# ADF4351_PLL.net
KiCad netlist of a schematic drawn in Altium Designer
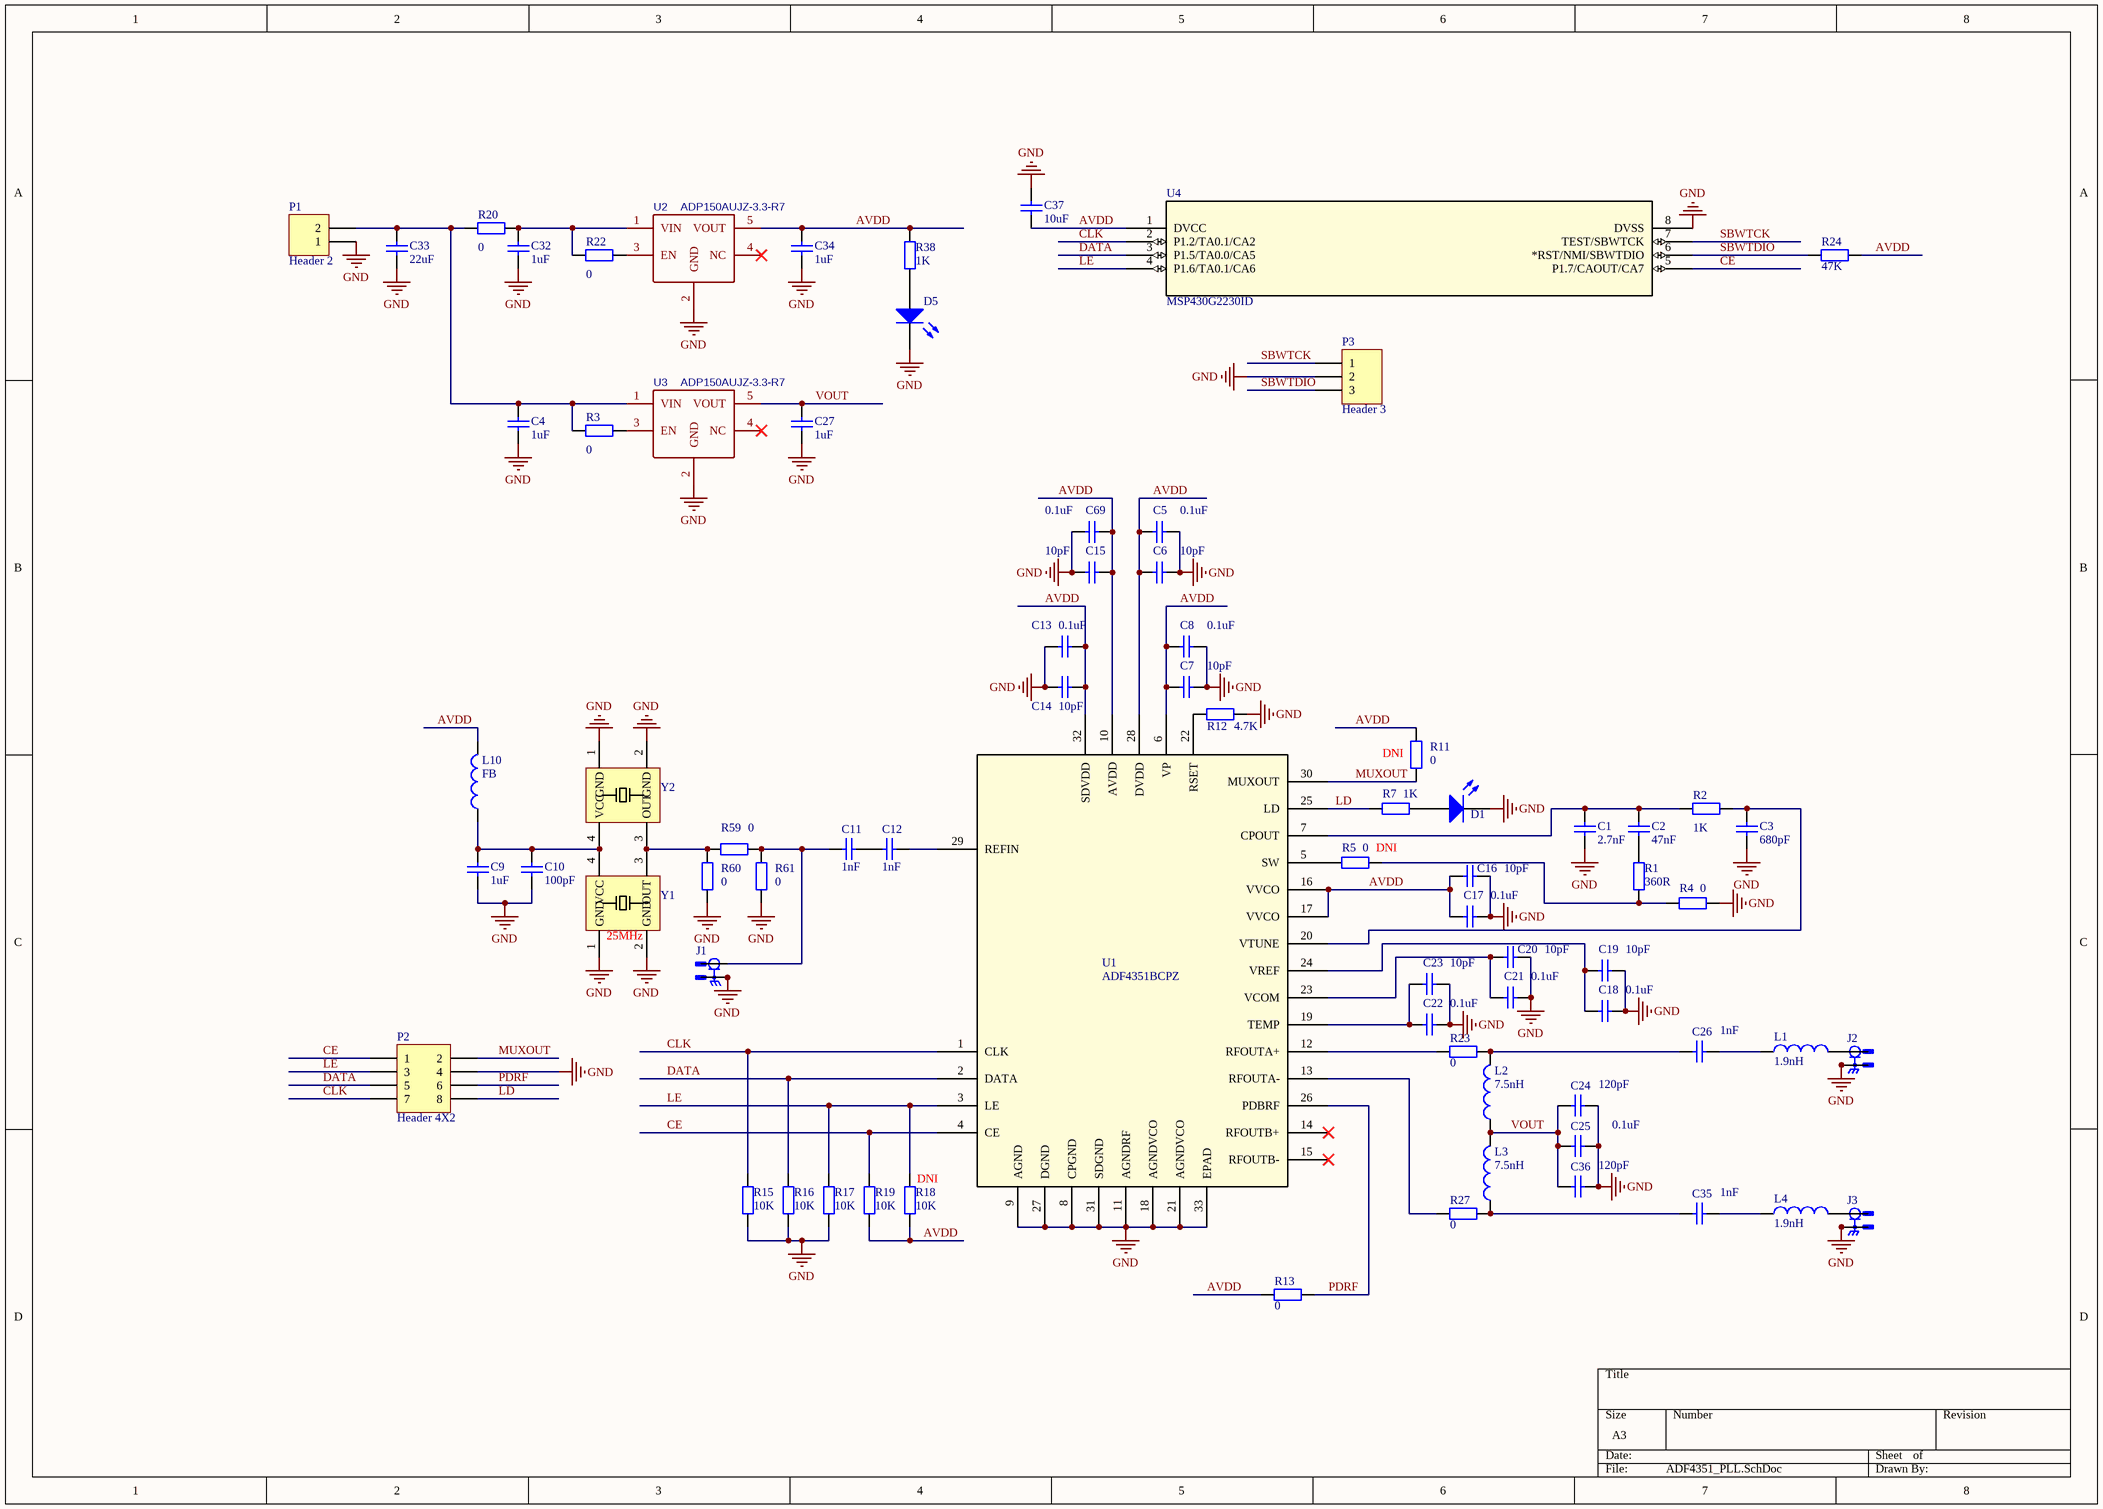
[diagram p0: ADF4351_PLL.SchDoc]

(export (version "E")
  (design (tool "Eeschema 10.0.6"))
  (components
    (comp (ref "C1")
      (value "2.7nF")
      (footprint "0603E")
      (description "Capacitor")
      (fields (field (name "Comment") "Cap") (field (name "PUBLISHER") "Altium Limited"))
      (libsource (lib "Miscellaneous Devices") (part "Cap"))
    )
    (comp (ref "C2")
      (value "47nF")
      (footprint "0603E")
      (description "Capacitor")
      (fields (field (name "Comment") "Cap") (field (name "PUBLISHER") "Altium Limited"))
      (libsource (lib "Miscellaneous Devices") (part "Cap"))
    )
    (comp (ref "C3")
      (value "680pF")
      (footprint "0603E")
      (description "Capacitor")
      (fields (field (name "Comment") "Cap") (field (name "PUBLISHER") "Altium Limited"))
      (libsource (lib "Miscellaneous Devices") (part "Cap"))
    )
    (comp (ref "C4")
      (value "1uF")
      (footprint "0603E")
      (description "Capacitor")
      (fields (field (name "Comment") "Cap") (field (name "PUBLISHER") "Altium Limited"))
      (libsource (lib "Miscellaneous Devices") (part "Cap"))
    )
    (comp (ref "C5")
      (value "0.1uF")
      (footprint "0603E")
      (description "Capacitor")
      (fields (field (name "Comment") "Cap") (field (name "PUBLISHER") "Altium Limited"))
      (libsource (lib "Miscellaneous Devices") (part "Cap"))
    )
    (comp (ref "C6")
      (value "10pF")
      (footprint "0603E")
      (description "Capacitor")
      (fields (field (name "Comment") "Cap") (field (name "PUBLISHER") "Altium Limited"))
      (libsource (lib "Miscellaneous Devices") (part "Cap"))
    )
    (comp (ref "C7")
      (value "10pF")
      (footprint "0603E")
      (description "Capacitor")
      (fields (field (name "Comment") "Cap") (field (name "PUBLISHER") "Altium Limited"))
      (libsource (lib "Miscellaneous Devices") (part "Cap"))
    )
    (comp (ref "C8")
      (value "0.1uF")
      (footprint "0603E")
      (description "Capacitor")
      (fields (field (name "Comment") "Cap") (field (name "PUBLISHER") "Altium Limited"))
      (libsource (lib "Miscellaneous Devices") (part "Cap"))
    )
    (comp (ref "C9")
      (value "1uF")
      (footprint "0603E")
      (description "Capacitor")
      (fields (field (name "Comment") "Cap") (field (name "PUBLISHER") "Altium Limited"))
      (libsource (lib "Miscellaneous Devices") (part "Cap"))
    )
    (comp (ref "C10")
      (value "100pF")
      (footprint "0603E")
      (description "Capacitor")
      (fields (field (name "Comment") "Cap") (field (name "PUBLISHER") "Altium Limited"))
      (libsource (lib "Miscellaneous Devices") (part "Cap"))
    )
    (comp (ref "C11")
      (value "1nF")
      (footprint "0603E")
      (description "Capacitor")
      (fields (field (name "Comment") "Cap") (field (name "PUBLISHER") "Altium Limited"))
      (libsource (lib "Miscellaneous Devices") (part "Cap"))
    )
    (comp (ref "C12")
      (value "1nF")
      (footprint "0603E")
      (description "Capacitor")
      (fields (field (name "Comment") "Cap") (field (name "PUBLISHER") "Altium Limited"))
      (libsource (lib "Miscellaneous Devices") (part "Cap"))
    )
    (comp (ref "C13")
      (value "0.1uF")
      (footprint "0603E")
      (description "Capacitor")
      (fields (field (name "Comment") "Cap") (field (name "PUBLISHER") "Altium Limited"))
      (libsource (lib "Miscellaneous Devices") (part "Cap"))
    )
    (comp (ref "C14")
      (value "10pF")
      (footprint "0603E")
      (description "Capacitor")
      (fields (field (name "Comment") "Cap") (field (name "PUBLISHER") "Altium Limited"))
      (libsource (lib "Miscellaneous Devices") (part "Cap"))
    )
    (comp (ref "C15")
      (value "10pF")
      (footprint "0603E")
      (description "Capacitor")
      (fields (field (name "Comment") "Cap") (field (name "PUBLISHER") "Altium Limited"))
      (libsource (lib "Miscellaneous Devices") (part "Cap"))
    )
    (comp (ref "C16")
      (value "10pF")
      (footprint "0603E")
      (description "Capacitor")
      (fields (field (name "Comment") "Cap") (field (name "PUBLISHER") "Altium Limited"))
      (libsource (lib "Miscellaneous Devices") (part "Cap"))
    )
    (comp (ref "C17")
      (value "0.1uF")
      (footprint "0603E")
      (description "Capacitor")
      (fields (field (name "Comment") "Cap") (field (name "PUBLISHER") "Altium Limited"))
      (libsource (lib "Miscellaneous Devices") (part "Cap"))
    )
    (comp (ref "C18")
      (value "0.1uF")
      (footprint "0603E")
      (description "Capacitor")
      (fields (field (name "Comment") "Cap") (field (name "PUBLISHER") "Altium Limited"))
      (libsource (lib "Miscellaneous Devices") (part "Cap"))
    )
    (comp (ref "C19")
      (value "10pF")
      (footprint "0603E")
      (description "Capacitor")
      (fields (field (name "Comment") "Cap") (field (name "PUBLISHER") "Altium Limited"))
      (libsource (lib "Miscellaneous Devices") (part "Cap"))
    )
    (comp (ref "C20")
      (value "10pF")
      (footprint "0603E")
      (description "Capacitor")
      (fields (field (name "Comment") "Cap") (field (name "PUBLISHER") "Altium Limited"))
      (libsource (lib "Miscellaneous Devices") (part "Cap"))
    )
    (comp (ref "C21")
      (value "0.1uF")
      (footprint "0603E")
      (description "Capacitor")
      (fields (field (name "Comment") "Cap") (field (name "PUBLISHER") "Altium Limited"))
      (libsource (lib "Miscellaneous Devices") (part "Cap"))
    )
    (comp (ref "C22")
      (value "0.1uF")
      (footprint "0603E")
      (description "Capacitor")
      (fields (field (name "Comment") "Cap") (field (name "PUBLISHER") "Altium Limited"))
      (libsource (lib "Miscellaneous Devices") (part "Cap"))
    )
    (comp (ref "C23")
      (value "10pF")
      (footprint "0603E")
      (description "Capacitor")
      (fields (field (name "Comment") "Cap") (field (name "PUBLISHER") "Altium Limited"))
      (libsource (lib "Miscellaneous Devices") (part "Cap"))
    )
    (comp (ref "C24")
      (value "120pF")
      (footprint "0603E")
      (description "Capacitor")
      (fields (field (name "Comment") "Cap") (field (name "PUBLISHER") "Altium Limited"))
      (libsource (lib "Miscellaneous Devices") (part "Cap"))
    )
    (comp (ref "C25")
      (value "0.1uF")
      (footprint "0603E")
      (description "Capacitor")
      (fields (field (name "Comment") "Cap") (field (name "PUBLISHER") "Altium Limited"))
      (libsource (lib "Miscellaneous Devices") (part "Cap"))
    )
    (comp (ref "C26")
      (value "1nF")
      (footprint "0603E")
      (description "Capacitor")
      (fields (field (name "Comment") "Cap") (field (name "PUBLISHER") "Altium Limited"))
      (libsource (lib "Miscellaneous Devices") (part "Cap"))
    )
    (comp (ref "C27")
      (value "1uF")
      (footprint "0603E")
      (description "Capacitor")
      (fields (field (name "Comment") "Cap") (field (name "PUBLISHER") "Altium Limited"))
      (libsource (lib "Miscellaneous Devices") (part "Cap"))
    )
    (comp (ref "C32")
      (value "1uF")
      (footprint "0603E")
      (description "Capacitor")
      (fields (field (name "Comment") "Cap") (field (name "PUBLISHER") "Altium Limited"))
      (libsource (lib "Miscellaneous Devices") (part "Cap"))
    )
    (comp (ref "C33")
      (value "22uF")
      (footprint "R1206")
      (description "Capacitor")
      (fields (field (name "Comment") "Cap") (field (name "PUBLISHER") "Altium Limited"))
      (libsource (lib "Miscellaneous Devices") (part "Cap"))
    )
    (comp (ref "C34")
      (value "1uF")
      (footprint "0603E")
      (description "Capacitor")
      (fields (field (name "Comment") "Cap") (field (name "PUBLISHER") "Altium Limited"))
      (libsource (lib "Miscellaneous Devices") (part "Cap"))
    )
    (comp (ref "C35")
      (value "1nF")
      (footprint "0603E")
      (description "Capacitor")
      (fields (field (name "Comment") "Cap") (field (name "PUBLISHER") "Altium Limited"))
      (libsource (lib "Miscellaneous Devices") (part "Cap"))
    )
    (comp (ref "C36")
      (value "120pF")
      (footprint "0603E")
      (description "Capacitor")
      (fields (field (name "Comment") "Cap") (field (name "PUBLISHER") "Altium Limited"))
      (libsource (lib "Miscellaneous Devices") (part "Cap"))
    )
    (comp (ref "C37")
      (value "10uF")
      (footprint "0603E")
      (description "Capacitor")
      (fields (field (name "Comment") "Cap") (field (name "PUBLISHER") "Altium Limited"))
      (libsource (lib "Miscellaneous Devices") (part "Cap"))
    )
    (comp (ref "C69")
      (value "0.1uF")
      (footprint "0603E")
      (description "Capacitor")
      (fields (field (name "Comment") "Cap") (field (name "PUBLISHER") "Altium Limited"))
      (libsource (lib "Miscellaneous Devices") (part "Cap"))
    )
    (comp (ref "D1")
      (value "LED0")
      (footprint "0603E")
      (description "Typical INFRARED GaAs LED")
      (fields (field (name "PUBLISHER") "Altium Limited"))
      (libsource (lib "Miscellaneous Devices") (part "LED0"))
    )
    (comp (ref "D5")
      (value "LED0")
      (footprint "0603E")
      (description "Typical INFRARED GaAs LED")
      (fields (field (name "PUBLISHER") "Altium Limited"))
      (libsource (lib "Miscellaneous Devices") (part "LED0"))
    )
    (comp (ref "J1")
      (value "~")
      (footprint "SMA")
      (description "SMA Connector Plug, Male Pin 50Ohm Board Edge, End Launch; Panel Mount Solder")
      (fields (field (name "MF") "Linx") (field (name "MP") "CONSMA013.031"))
      (libsource (lib "") (part "CONSMA013.031_1"))
    )
    (comp (ref "J2")
      (value "~")
      (footprint "SMA")
      (description "SMA Connector Plug, Male Pin 50Ohm Board Edge, End Launch; Panel Mount Solder")
      (fields (field (name "MF") "Linx") (field (name "MP") "CONSMA013.031"))
      (libsource (lib "SMA") (part "CONSMA013.031"))
    )
    (comp (ref "J3")
      (value "~")
      (footprint "SMA")
      (description "SMA Connector Plug, Male Pin 50Ohm Board Edge, End Launch; Panel Mount Solder")
      (fields (field (name "MF") "Linx") (field (name "MP") "CONSMA013.031"))
      (libsource (lib "SMA") (part "CONSMA013.031"))
    )
    (comp (ref "L1")
      (value "1.9nH")
      (footprint "0603E")
      (description "Inductor")
      (fields (field (name "PUBLISHER") "Altium Limited"))
      (libsource (lib "Miscellaneous Devices") (part "Inductor"))
    )
    (comp (ref "L2")
      (value "7.5nH")
      (footprint "0603E")
      (description "Inductor")
      (fields (field (name "PUBLISHER") "Altium Limited"))
      (libsource (lib "Miscellaneous Devices") (part "Inductor"))
    )
    (comp (ref "L3")
      (value "7.5nH")
      (footprint "0603E")
      (description "Inductor")
      (fields (field (name "PUBLISHER") "Altium Limited"))
      (libsource (lib "Miscellaneous Devices") (part "Inductor"))
    )
    (comp (ref "L4")
      (value "1.9nH")
      (footprint "0603E")
      (description "Inductor")
      (fields (field (name "PUBLISHER") "Altium Limited"))
      (libsource (lib "Miscellaneous Devices") (part "Inductor"))
    )
    (comp (ref "L10")
      (value "FB")
      (footprint "0603E")
      (description "Inductor")
      (fields (field (name "PUBLISHER") "Altium Limited"))
      (libsource (lib "Miscellaneous Devices") (part "Inductor"))
    )
    (comp (ref "P1")
      (value "Header 2")
      (footprint "HDR1X2")
      (description "Header, 2-Pin")
      (fields (field (name "PUBLISHER") "Altium Limited"))
      (libsource (lib "Miscellaneous Connectors") (part "Header 2"))
    )
    (comp (ref "P2")
      (value "Header 4X2")
      (footprint "HDR2X4")
      (description "Header, 4-Pin, Dual row")
      (fields (field (name "PUBLISHER") "Altium Limited"))
      (libsource (lib "Miscellaneous Connectors") (part "Header 4X2"))
    )
    (comp (ref "P3")
      (value "Header 3")
      (footprint "HDR1X3")
      (description "Header, 3-Pin")
      (fields (field (name "PUBLISHER") "Altium Limited"))
      (libsource (lib "Miscellaneous Connectors") (part "Header 3"))
    )
    (comp (ref "R1")
      (value "360R")
      (footprint "0603E")
      (description "Resistor")
      (fields (field (name "Comment") "Res2") (field (name "PUBLISHER") "Altium Limited"))
      (libsource (lib "Miscellaneous Devices") (part "Res2"))
    )
    (comp (ref "R2")
      (value "1K")
      (footprint "0603E")
      (description "Resistor")
      (fields (field (name "Comment") "Res2") (field (name "PUBLISHER") "Altium Limited"))
      (libsource (lib "") (part "Res2_2"))
    )
    (comp (ref "R3")
      (value "0")
      (footprint "0603E")
      (description "Resistor")
      (fields (field (name "Comment") "Res2") (field (name "PUBLISHER") "Altium Limited"))
      (libsource (lib "") (part "Res2_2"))
    )
    (comp (ref "R4")
      (value "0")
      (footprint "0603E")
      (description "Resistor")
      (fields (field (name "Comment") "Res2") (field (name "PUBLISHER") "Altium Limited"))
      (libsource (lib "") (part "Res2_2"))
    )
    (comp (ref "R5")
      (value "0")
      (footprint "0603E")
      (description "Resistor")
      (fields (field (name "Comment") "Res2") (field (name "PUBLISHER") "Altium Limited"))
      (libsource (lib "") (part "Res2_2"))
    )
    (comp (ref "R7")
      (value "1K")
      (footprint "0603E")
      (description "Resistor")
      (fields (field (name "Comment") "Res2") (field (name "PUBLISHER") "Altium Limited"))
      (libsource (lib "") (part "Res2_2"))
    )
    (comp (ref "R11")
      (value "0")
      (footprint "0603E")
      (description "Resistor")
      (fields (field (name "Comment") "Res2") (field (name "PUBLISHER") "Altium Limited"))
      (libsource (lib "Miscellaneous Devices") (part "Res2"))
    )
    (comp (ref "R12")
      (value "4.7K")
      (footprint "0603E")
      (description "Resistor")
      (fields (field (name "Comment") "Res2") (field (name "PUBLISHER") "Altium Limited"))
      (libsource (lib "") (part "Res2_1"))
    )
    (comp (ref "R13")
      (value "0")
      (footprint "0603E")
      (description "Resistor")
      (fields (field (name "Comment") "Res2") (field (name "PUBLISHER") "Altium Limited"))
      (libsource (lib "") (part "Res2_1"))
    )
    (comp (ref "R15")
      (value "10K")
      (footprint "0603E")
      (description "Resistor")
      (fields (field (name "Comment") "Res2") (field (name "PUBLISHER") "Altium Limited"))
      (libsource (lib "Miscellaneous Devices") (part "Res2"))
    )
    (comp (ref "R16")
      (value "10K")
      (footprint "0603E")
      (description "Resistor")
      (fields (field (name "Comment") "Res2") (field (name "PUBLISHER") "Altium Limited"))
      (libsource (lib "Miscellaneous Devices") (part "Res2"))
    )
    (comp (ref "R17")
      (value "10K")
      (footprint "0603E")
      (description "Resistor")
      (fields (field (name "Comment") "Res2") (field (name "PUBLISHER") "Altium Limited"))
      (libsource (lib "Miscellaneous Devices") (part "Res2"))
    )
    (comp (ref "R18")
      (value "10K")
      (footprint "0603E")
      (description "Resistor")
      (fields (field (name "Comment") "Res2") (field (name "PUBLISHER") "Altium Limited"))
      (libsource (lib "Miscellaneous Devices") (part "Res2"))
    )
    (comp (ref "R19")
      (value "10K")
      (footprint "0603E")
      (description "Resistor")
      (fields (field (name "Comment") "Res2") (field (name "PUBLISHER") "Altium Limited"))
      (libsource (lib "Miscellaneous Devices") (part "Res2"))
    )
    (comp (ref "R20")
      (value "0")
      (footprint "0603E")
      (description "Resistor")
      (fields (field (name "Comment") "Res2") (field (name "PUBLISHER") "Altium Limited"))
      (libsource (lib "") (part "Res2_2"))
    )
    (comp (ref "R22")
      (value "0")
      (footprint "0603E")
      (description "Resistor")
      (fields (field (name "Comment") "Res2") (field (name "PUBLISHER") "Altium Limited"))
      (libsource (lib "") (part "Res2_2"))
    )
    (comp (ref "R23")
      (value "0")
      (footprint "0603E")
      (description "Resistor")
      (fields (field (name "Comment") "Res2") (field (name "PUBLISHER") "Altium Limited"))
      (libsource (lib "") (part "Res2_1"))
    )
    (comp (ref "R24")
      (value "47K")
      (footprint "0603E")
      (description "Resistor")
      (fields (field (name "Comment") "Res2") (field (name "PUBLISHER") "Altium Limited"))
      (libsource (lib "") (part "Res2_2"))
    )
    (comp (ref "R27")
      (value "0")
      (footprint "0603E")
      (description "Resistor")
      (fields (field (name "Comment") "Res2") (field (name "PUBLISHER") "Altium Limited"))
      (libsource (lib "") (part "Res2_1"))
    )
    (comp (ref "R38")
      (value "1K")
      (footprint "0603E")
      (description "Resistor")
      (fields (field (name "Comment") "Res2") (field (name "PUBLISHER") "Altium Limited"))
      (libsource (lib "Miscellaneous Devices") (part "Res2"))
    )
    (comp (ref "R59")
      (value "0")
      (footprint "0603E")
      (description "Resistor")
      (fields (field (name "Comment") "Res2") (field (name "PUBLISHER") "Altium Limited"))
      (libsource (lib "") (part "Res2_2"))
    )
    (comp (ref "R60")
      (value "0")
      (footprint "0603E")
      (description "Resistor")
      (fields (field (name "Comment") "Res2") (field (name "PUBLISHER") "Altium Limited"))
      (libsource (lib "Miscellaneous Devices") (part "Res2"))
    )
    (comp (ref "R61")
      (value "0")
      (footprint "0603E")
      (description "Resistor")
      (fields (field (name "Comment") "Res2") (field (name "PUBLISHER") "Altium Limited"))
      (libsource (lib "Miscellaneous Devices") (part "Res2"))
    )
    (comp (ref "U1")
      (value "ADF4351BCPZ")
      (footprint "CP-32-7_ADI")
      (description "No Description Available")
      (fields (field (name "COPYRIGHT") "Copyright (C) 2021 Accelerated Designs. All rights reserved"))
      (libsource (lib "ADF4351BCPZ") (part "ADF4351BCPZ"))
    )
    (comp (ref "U2")
      (value "ADP150AUJZ-3.3-R7")
      (footprint "SOT-23-5_L3.0-W1.7-P0.95-LS2.8-BR")
      (fields (field (name "BOM_SUPPLIER PART") "C29149"))
      (libsource (lib "ADP150") (part "ADP150AUJZ-3.3-R7"))
    )
    (comp (ref "U3")
      (value "ADP150AUJZ-3.3-R7")
      (footprint "SOT-23-5_L3.0-W1.7-P0.95-LS2.8-BR")
      (fields (field (name "BOM_SUPPLIER PART") "C29149"))
      (libsource (lib "ADP150") (part "ADP150AUJZ-3.3-R7"))
    )
    (comp (ref "U4")
      (value "MSP430G2230ID")
      (footprint "D8")
      (description "No Description Available")
      (fields (field (name "COPYRIGHT") "Copyright (C) 2022 Ultra Librarian. All rights reserved."))
      (libsource (lib "MSP430G2230ID") (part "MSP430G2230ID"))
    )
    (comp (ref "Y1") (value "DSB321SDA") (footprint "3225") (libsource (lib "ADF4351") (part "DSB321SDA")))
    (comp (ref "Y2") (value "DSB321SDA") (footprint "2016") (libsource (lib "") (part "DSB321SDA_1")))
  )
  (nets
    (net (code "1") (name "/AVDD") (class "Default")
      (node (ref "C13") (pin "1") (pinfunction "1_1") (pintype "passive"))
      (node (ref "C14") (pin "1") (pinfunction "1_1") (pintype "passive"))
      (node (ref "C15") (pin "1") (pinfunction "1_1") (pintype "passive"))
      (node (ref "C16") (pin "1") (pinfunction "1_1") (pintype "passive"))
      (node (ref "C17") (pin "1") (pinfunction "1_1") (pintype "passive"))
      (node (ref "C34") (pin "1") (pinfunction "1_1") (pintype "passive"))
      (node (ref "C37") (pin "1") (pinfunction "1_1") (pintype "passive"))
      (node (ref "C5") (pin "1") (pinfunction "1_1") (pintype "passive"))
      (node (ref "C6") (pin "1") (pinfunction "1_1") (pintype "passive"))
      (node (ref "C69") (pin "1") (pinfunction "1_1") (pintype "passive"))
      (node (ref "C7") (pin "1") (pinfunction "1_1") (pintype "passive"))
      (node (ref "C8") (pin "1") (pinfunction "1_1") (pintype "passive"))
      (node (ref "L10") (pin "2") (pinfunction "2_2") (pintype "passive"))
      (node (ref "R11") (pin "2") (pinfunction "2_2") (pintype "passive"))
      (node (ref "R13") (pin "2") (pinfunction "2_2") (pintype "passive"))
      (node (ref "R18") (pin "1") (pinfunction "1_1") (pintype "passive"))
      (node (ref "R19") (pin "1") (pinfunction "1_1") (pintype "passive"))
      (node (ref "R24") (pin "2") (pinfunction "2_2") (pintype "passive"))
      (node (ref "R38") (pin "2") (pinfunction "2_2") (pintype "passive"))
      (node (ref "U1") (pin "10") (pinfunction "AVDD_10") (pintype "passive"))
      (node (ref "U1") (pin "16") (pinfunction "VVCO_16") (pintype "passive"))
      (node (ref "U1") (pin "17") (pinfunction "VVCO_17") (pintype "passive"))
      (node (ref "U1") (pin "28") (pinfunction "DVDD_28") (pintype "passive"))
      (node (ref "U1") (pin "32") (pinfunction "SDVDD_32") (pintype "passive"))
      (node (ref "U1") (pin "6") (pinfunction "VP_6") (pintype "passive"))
      (node (ref "U2") (pin "5") (pinfunction "VOUT_5") (pintype "passive"))
      (node (ref "U4") (pin "1") (pinfunction "DVCC_1") (pintype "power_in"))
    )
    (net (code "2") (name "/CE") (class "Default")
      (node (ref "P2") (pin "1") (pinfunction "1_1") (pintype "passive"))
      (node (ref "R19") (pin "2") (pinfunction "2_2") (pintype "passive"))
      (node (ref "U1") (pin "4") (pinfunction "CE_4") (pintype "passive"))
      (node (ref "U4") (pin "5") (pinfunction "P1.7/CAOUT/CA7_5") (pintype "bidirectional"))
    )
    (net (code "3") (name "/CLK") (class "Default")
      (node (ref "P2") (pin "7") (pinfunction "7_7") (pintype "passive"))
      (node (ref "R15") (pin "2") (pinfunction "2_2") (pintype "passive"))
      (node (ref "U1") (pin "1") (pinfunction "CLK_1") (pintype "passive"))
      (node (ref "U4") (pin "2") (pinfunction "P1.2/TA0.1/CA2_2") (pintype "bidirectional"))
    )
    (net (code "4") (name "/DATA") (class "Default")
      (node (ref "P2") (pin "5") (pinfunction "5_5") (pintype "passive"))
      (node (ref "R16") (pin "2") (pinfunction "2_2") (pintype "passive"))
      (node (ref "U1") (pin "2") (pinfunction "DATA_2") (pintype "passive"))
      (node (ref "U4") (pin "3") (pinfunction "P1.5/TA0.0/CA5_3") (pintype "bidirectional"))
    )
    (net (code "5") (name "/LD") (class "Default")
      (node (ref "P2") (pin "8") (pinfunction "8_8") (pintype "passive"))
      (node (ref "R7") (pin "1") (pinfunction "1_1") (pintype "passive"))
      (node (ref "U1") (pin "25") (pinfunction "LD_25") (pintype "passive"))
    )
    (net (code "6") (name "/LE") (class "Default")
      (node (ref "P2") (pin "3") (pinfunction "3_3") (pintype "passive"))
      (node (ref "R17") (pin "2") (pinfunction "2_2") (pintype "passive"))
      (node (ref "R18") (pin "2") (pinfunction "2_2") (pintype "passive"))
      (node (ref "U1") (pin "3") (pinfunction "LE_3") (pintype "passive"))
      (node (ref "U4") (pin "4") (pinfunction "P1.6/TA0.1/CA6_4") (pintype "bidirectional"))
    )
    (net (code "7") (name "/MUXOUT") (class "Default")
      (node (ref "P2") (pin "2") (pinfunction "2_2") (pintype "passive"))
      (node (ref "R11") (pin "1") (pinfunction "1_1") (pintype "passive"))
      (node (ref "U1") (pin "30") (pinfunction "MUXOUT_30") (pintype "passive"))
    )
    (net (code "8") (name "/PDRF") (class "Default")
      (node (ref "P2") (pin "6") (pinfunction "6_6") (pintype "passive"))
      (node (ref "R13") (pin "1") (pinfunction "1_1") (pintype "passive"))
      (node (ref "U1") (pin "26") (pinfunction "PDBRF_26") (pintype "passive"))
    )
    (net (code "9") (name "/SBWTCK") (class "Default")
      (node (ref "P3") (pin "1") (pinfunction "1_1") (pintype "passive"))
      (node (ref "U4") (pin "7") (pinfunction "TEST/SBWTCK_7") (pintype "bidirectional"))
    )
    (net (code "10") (name "/SBWTDIO") (class "Default")
      (node (ref "P3") (pin "3") (pinfunction "3_3") (pintype "passive"))
      (node (ref "R24") (pin "1") (pinfunction "1_1") (pintype "passive"))
      (node (ref "U4") (pin "6") (pinfunction "*RST/NMI/SBWTDIO_6") (pintype "bidirectional"))
    )
    (net (code "11") (name "/VOUT") (class "Default")
      (node (ref "C24") (pin "1") (pinfunction "1_1") (pintype "passive"))
      (node (ref "C25") (pin "1") (pinfunction "1_1") (pintype "passive"))
      (node (ref "C27") (pin "1") (pinfunction "1_1") (pintype "passive"))
      (node (ref "C36") (pin "1") (pinfunction "1_1") (pintype "passive"))
      (node (ref "L2") (pin "1") (pinfunction "1_1") (pintype "passive"))
      (node (ref "L3") (pin "2") (pinfunction "2_2") (pintype "passive"))
      (node (ref "U3") (pin "5") (pinfunction "VOUT_5") (pintype "passive"))
    )
    (net (code "12") (name "GND") (class "Default")
      (node (ref "C1") (pin "1") (pinfunction "1_1") (pintype "passive"))
      (node (ref "C10") (pin "2") (pinfunction "2_2") (pintype "passive"))
      (node (ref "C13") (pin "2") (pinfunction "2_2") (pintype "passive"))
      (node (ref "C14") (pin "2") (pinfunction "2_2") (pintype "passive"))
      (node (ref "C15") (pin "2") (pinfunction "2_2") (pintype "passive"))
      (node (ref "C16") (pin "2") (pinfunction "2_2") (pintype "passive"))
      (node (ref "C17") (pin "2") (pinfunction "2_2") (pintype "passive"))
      (node (ref "C18") (pin "2") (pinfunction "2_2") (pintype "passive"))
      (node (ref "C19") (pin "2") (pinfunction "2_2") (pintype "passive"))
      (node (ref "C20") (pin "2") (pinfunction "2_2") (pintype "passive"))
      (node (ref "C21") (pin "2") (pinfunction "2_2") (pintype "passive"))
      (node (ref "C22") (pin "2") (pinfunction "2_2") (pintype "passive"))
      (node (ref "C23") (pin "2") (pinfunction "2_2") (pintype "passive"))
      (node (ref "C24") (pin "2") (pinfunction "2_2") (pintype "passive"))
      (node (ref "C25") (pin "2") (pinfunction "2_2") (pintype "passive"))
      (node (ref "C27") (pin "2") (pinfunction "2_2") (pintype "passive"))
      (node (ref "C3") (pin "1") (pinfunction "1_1") (pintype "passive"))
      (node (ref "C32") (pin "2") (pinfunction "2_2") (pintype "passive"))
      (node (ref "C33") (pin "2") (pinfunction "2_2") (pintype "passive"))
      (node (ref "C34") (pin "2") (pinfunction "2_2") (pintype "passive"))
      (node (ref "C36") (pin "2") (pinfunction "2_2") (pintype "passive"))
      (node (ref "C37") (pin "2") (pinfunction "2_2") (pintype "passive"))
      (node (ref "C4") (pin "2") (pinfunction "2_2") (pintype "passive"))
      (node (ref "C5") (pin "2") (pinfunction "2_2") (pintype "passive"))
      (node (ref "C6") (pin "2") (pinfunction "2_2") (pintype "passive"))
      (node (ref "C69") (pin "2") (pinfunction "2_2") (pintype "passive"))
      (node (ref "C7") (pin "2") (pinfunction "2_2") (pintype "passive"))
      (node (ref "C8") (pin "2") (pinfunction "2_2") (pintype "passive"))
      (node (ref "C9") (pin "2") (pinfunction "2_2") (pintype "passive"))
      (node (ref "D1") (pin "2") (pinfunction "K_2") (pintype "passive"))
      (node (ref "D5") (pin "2") (pinfunction "K_2") (pintype "passive"))
      (node (ref "J1") (pin "S1") (pinfunction "2_S1") (pintype "passive"))
      (node (ref "J1") (pin "S2") (pinfunction "2_S2") (pintype "passive"))
      (node (ref "J1") (pin "S3") (pinfunction "2_S3") (pintype "passive"))
      (node (ref "J1") (pin "S4") (pinfunction "2_S4") (pintype "passive"))
      (node (ref "J2") (pin "S1") (pinfunction "2_S1") (pintype "passive"))
      (node (ref "J2") (pin "S2") (pinfunction "2_S2") (pintype "passive"))
      (node (ref "J2") (pin "S3") (pinfunction "2_S3") (pintype "passive"))
      (node (ref "J2") (pin "S4") (pinfunction "2_S4") (pintype "passive"))
      (node (ref "J3") (pin "S1") (pinfunction "2_S1") (pintype "passive"))
      (node (ref "J3") (pin "S2") (pinfunction "2_S2") (pintype "passive"))
      (node (ref "J3") (pin "S3") (pinfunction "2_S3") (pintype "passive"))
      (node (ref "J3") (pin "S4") (pinfunction "2_S4") (pintype "passive"))
      (node (ref "P1") (pin "1") (pinfunction "1_1") (pintype "passive"))
      (node (ref "P2") (pin "4") (pinfunction "4_4") (pintype "passive"))
      (node (ref "P3") (pin "2") (pinfunction "2_2") (pintype "passive"))
      (node (ref "R12") (pin "1") (pinfunction "1_1") (pintype "passive"))
      (node (ref "R15") (pin "1") (pinfunction "1_1") (pintype "passive"))
      (node (ref "R16") (pin "1") (pinfunction "1_1") (pintype "passive"))
      (node (ref "R17") (pin "1") (pinfunction "1_1") (pintype "passive"))
      (node (ref "R4") (pin "2") (pinfunction "2_2") (pintype "passive"))
      (node (ref "R60") (pin "1") (pinfunction "1_1") (pintype "passive"))
      (node (ref "R61") (pin "1") (pinfunction "1_1") (pintype "passive"))
      (node (ref "U1") (pin "11") (pinfunction "AGNDRF_11") (pintype "passive"))
      (node (ref "U1") (pin "18") (pinfunction "AGNDVCO_18") (pintype "passive"))
      (node (ref "U1") (pin "21") (pinfunction "AGNDVCO_21") (pintype "passive"))
      (node (ref "U1") (pin "27") (pinfunction "DGND_27") (pintype "passive"))
      (node (ref "U1") (pin "31") (pinfunction "SDGND_31") (pintype "passive"))
      (node (ref "U1") (pin "33") (pinfunction "EPAD_33") (pintype "passive"))
      (node (ref "U1") (pin "8") (pinfunction "CPGND_8") (pintype "passive"))
      (node (ref "U1") (pin "9") (pinfunction "AGND_9") (pintype "passive"))
      (node (ref "U2") (pin "2") (pinfunction "GND_2") (pintype "passive"))
      (node (ref "U3") (pin "2") (pinfunction "GND_2") (pintype "passive"))
      (node (ref "U4") (pin "8") (pinfunction "DVSS_8") (pintype "power_in"))
      (node (ref "Y1") (pin "1") (pinfunction "GND_1") (pintype "passive"))
      (node (ref "Y1") (pin "2") (pinfunction "GND_2") (pintype "passive"))
      (node (ref "Y2") (pin "1") (pinfunction "GND_1") (pintype "passive"))
      (node (ref "Y2") (pin "2") (pinfunction "GND_2") (pintype "passive"))
    )
    (net (code "13") (name "Net-(C2-Pad1)") (class "Default")
      (node (ref "C2") (pin "1") (pinfunction "1_1") (pintype "passive"))
      (node (ref "R1") (pin "2") (pinfunction "2_2") (pintype "passive"))
    )
    (net (code "14") (name "Net-(C11-Pad1)") (class "Default")
      (node (ref "C11") (pin "1") (pinfunction "1_1") (pintype "passive"))
      (node (ref "J1") (pin "1") (pinfunction "1_1") (pintype "passive"))
      (node (ref "R59") (pin "2") (pinfunction "2_2") (pintype "passive"))
      (node (ref "R61") (pin "2") (pinfunction "2_2") (pintype "passive"))
    )
    (net (code "15") (name "Net-(C11-Pad2)") (class "Default")
      (node (ref "C11") (pin "2") (pinfunction "2_2") (pintype "passive"))
      (node (ref "C12") (pin "1") (pinfunction "1_1") (pintype "passive"))
    )
    (net (code "16") (name "Net-(C26-Pad1)") (class "Default")
      (node (ref "C26") (pin "1") (pinfunction "1_1") (pintype "passive"))
      (node (ref "L2") (pin "2") (pinfunction "2_2") (pintype "passive"))
      (node (ref "R23") (pin "1") (pinfunction "1_1") (pintype "passive"))
    )
    (net (code "17") (name "Net-(C26-Pad2)") (class "Default")
      (node (ref "C26") (pin "2") (pinfunction "2_2") (pintype "passive"))
      (node (ref "L1") (pin "1") (pinfunction "1_1") (pintype "passive"))
    )
    (net (code "18") (name "Net-(C35-Pad1)") (class "Default")
      (node (ref "C35") (pin "1") (pinfunction "1_1") (pintype "passive"))
      (node (ref "L3") (pin "1") (pinfunction "1_1") (pintype "passive"))
      (node (ref "R27") (pin "1") (pinfunction "1_1") (pintype "passive"))
    )
    (net (code "19") (name "Net-(C35-Pad2)") (class "Default")
      (node (ref "C35") (pin "2") (pinfunction "2_2") (pintype "passive"))
      (node (ref "L4") (pin "1") (pinfunction "1_1") (pintype "passive"))
    )
    (net (code "20") (name "Net-(D1-A)") (class "Default")
      (node (ref "D1") (pin "1") (pinfunction "A_1") (pintype "passive"))
      (node (ref "R7") (pin "2") (pinfunction "2_2") (pintype "passive"))
    )
    (net (code "21") (name "Net-(D5-A)") (class "Default")
      (node (ref "D5") (pin "1") (pinfunction "A_1") (pintype "passive"))
      (node (ref "R38") (pin "1") (pinfunction "1_1") (pintype "passive"))
    )
    (net (code "22") (name "Net-(J2-Pad1)") (class "Default")
      (node (ref "J2") (pin "1") (pinfunction "1_1") (pintype "passive"))
      (node (ref "L1") (pin "2") (pinfunction "2_2") (pintype "passive"))
    )
    (net (code "23") (name "Net-(J3-Pad1)") (class "Default")
      (node (ref "J3") (pin "1") (pinfunction "1_1") (pintype "passive"))
      (node (ref "L4") (pin "2") (pinfunction "2_2") (pintype "passive"))
    )
    (net (code "24") (name "Net-(R1-Pad1)") (class "Default")
      (node (ref "R1") (pin "1") (pinfunction "1_1") (pintype "passive"))
      (node (ref "R4") (pin "1") (pinfunction "1_1") (pintype "passive"))
      (node (ref "R5") (pin "2") (pinfunction "2_2") (pintype "passive"))
    )
    (net (code "25") (name "Net-(U1-CPOUT)") (class "Default")
      (node (ref "C1") (pin "2") (pinfunction "2_2") (pintype "passive"))
      (node (ref "C2") (pin "2") (pinfunction "2_2") (pintype "passive"))
      (node (ref "R2") (pin "1") (pinfunction "1_1") (pintype "passive"))
      (node (ref "U1") (pin "7") (pinfunction "CPOUT_7") (pintype "passive"))
    )
    (net (code "26") (name "Net-(U1-REFIN)") (class "Default")
      (node (ref "C12") (pin "2") (pinfunction "2_2") (pintype "passive"))
      (node (ref "U1") (pin "29") (pinfunction "REFIN_29") (pintype "passive"))
    )
    (net (code "27") (name "Net-(U1-RFOUTA+)") (class "Default")
      (node (ref "R23") (pin "2") (pinfunction "2_2") (pintype "passive"))
      (node (ref "U1") (pin "12") (pinfunction "RFOUTA+_12") (pintype "passive"))
    )
    (net (code "28") (name "Net-(U1-RFOUTA-)") (class "Default")
      (node (ref "R27") (pin "2") (pinfunction "2_2") (pintype "passive"))
      (node (ref "U1") (pin "13") (pinfunction "RFOUTA-_13") (pintype "passive"))
    )
    (net (code "29") (name "Net-(U1-RSET)") (class "Default")
      (node (ref "R12") (pin "2") (pinfunction "2_2") (pintype "passive"))
      (node (ref "U1") (pin "22") (pinfunction "RSET_22") (pintype "passive"))
    )
    (net (code "30") (name "Net-(U1-SW)") (class "Default")
      (node (ref "R5") (pin "1") (pinfunction "1_1") (pintype "passive"))
      (node (ref "U1") (pin "5") (pinfunction "SW_5") (pintype "passive"))
    )
    (net (code "31") (name "Net-(U1-TEMP)") (class "Default")
      (node (ref "C22") (pin "1") (pinfunction "1_1") (pintype "passive"))
      (node (ref "C23") (pin "1") (pinfunction "1_1") (pintype "passive"))
      (node (ref "U1") (pin "19") (pinfunction "TEMP_19") (pintype "passive"))
    )
    (net (code "32") (name "Net-(U1-VCOM)") (class "Default")
      (node (ref "C20") (pin "1") (pinfunction "1_1") (pintype "passive"))
      (node (ref "C21") (pin "1") (pinfunction "1_1") (pintype "passive"))
      (node (ref "U1") (pin "23") (pinfunction "VCOM_23") (pintype "passive"))
    )
    (net (code "33") (name "Net-(U1-VREF)") (class "Default")
      (node (ref "C18") (pin "1") (pinfunction "1_1") (pintype "passive"))
      (node (ref "C19") (pin "1") (pinfunction "1_1") (pintype "passive"))
      (node (ref "U1") (pin "24") (pinfunction "VREF_24") (pintype "passive"))
    )
    (net (code "34") (name "Net-(U1-VTUNE)") (class "Default")
      (node (ref "C3") (pin "2") (pinfunction "2_2") (pintype "passive"))
      (node (ref "R2") (pin "2") (pinfunction "2_2") (pintype "passive"))
      (node (ref "U1") (pin "20") (pinfunction "VTUNE_20") (pintype "passive"))
    )
    (net (code "35") (name "Net-(U2-EN)") (class "Default")
      (node (ref "R22") (pin "2") (pinfunction "2_2") (pintype "passive"))
      (node (ref "U2") (pin "3") (pinfunction "EN_3") (pintype "passive"))
    )
    (net (code "36") (name "Net-(U2-VIN)") (class "Default")
      (node (ref "C32") (pin "1") (pinfunction "1_1") (pintype "passive"))
      (node (ref "R20") (pin "2") (pinfunction "2_2") (pintype "passive"))
      (node (ref "R22") (pin "1") (pinfunction "1_1") (pintype "passive"))
      (node (ref "U2") (pin "1") (pinfunction "VIN_1") (pintype "passive"))
    )
    (net (code "37") (name "Net-(U3-EN)") (class "Default")
      (node (ref "R3") (pin "2") (pinfunction "2_2") (pintype "passive"))
      (node (ref "U3") (pin "3") (pinfunction "EN_3") (pintype "passive"))
    )
    (net (code "38") (name "Net-(U3-VIN)") (class "Default")
      (node (ref "C33") (pin "1") (pinfunction "1_1") (pintype "passive"))
      (node (ref "C4") (pin "1") (pinfunction "1_1") (pintype "passive"))
      (node (ref "P1") (pin "2") (pinfunction "2_2") (pintype "passive"))
      (node (ref "R20") (pin "1") (pinfunction "1_1") (pintype "passive"))
      (node (ref "R3") (pin "1") (pinfunction "1_1") (pintype "passive"))
      (node (ref "U3") (pin "1") (pinfunction "VIN_1") (pintype "passive"))
    )
    (net (code "39") (name "Net-(Y1-OUT)") (class "Default")
      (node (ref "R59") (pin "1") (pinfunction "1_1") (pintype "passive"))
      (node (ref "R60") (pin "2") (pinfunction "2_2") (pintype "passive"))
      (node (ref "Y1") (pin "3") (pinfunction "OUT_3") (pintype "passive"))
      (node (ref "Y2") (pin "3") (pinfunction "OUT_3") (pintype "passive"))
    )
    (net (code "40") (name "Net-(Y1-VCC)") (class "Default")
      (node (ref "C10") (pin "1") (pinfunction "1_1") (pintype "passive"))
      (node (ref "C9") (pin "1") (pinfunction "1_1") (pintype "passive"))
      (node (ref "L10") (pin "1") (pinfunction "1_1") (pintype "passive"))
      (node (ref "Y1") (pin "4") (pinfunction "VCC_4") (pintype "passive"))
      (node (ref "Y2") (pin "4") (pinfunction "VCC_4") (pintype "passive"))
    )
    (net (code "41") (name "unconnected-(U1-RFOUTB+-Pad14)") (class "Default")
      (node (ref "U1") (pin "14") (pinfunction "RFOUTB+_14") (pintype "passive+no_connect"))
    )
    (net (code "42") (name "unconnected-(U1-RFOUTB--Pad15)") (class "Default")
      (node (ref "U1") (pin "15") (pinfunction "RFOUTB-_15") (pintype "passive+no_connect"))
    )
    (net (code "43") (name "unconnected-(U2-NC-Pad4)") (class "Default")
      (node (ref "U2") (pin "4") (pinfunction "NC_4") (pintype "passive+no_connect"))
    )
    (net (code "44") (name "unconnected-(U3-NC-Pad4)") (class "Default")
      (node (ref "U3") (pin "4") (pinfunction "NC_4") (pintype "passive+no_connect"))
    )
  )
)
